# Side_PCB.net
KiCad netlist of a schematic drawn in Altium Designer
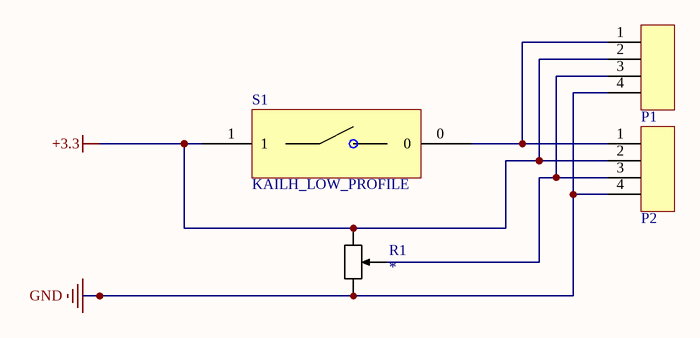
[diagram p0: Side_PCB.SchDoc]

(export (version "E")
  (design (tool "Eeschema 10.0.6"))
  (components
    (comp (ref "P1")
      (value "JST_SE_4PIN")
      (footprint "JST_SE_4PIN")
      (libsource (lib "FF_component_lib") (part "JST_SE_4PIN"))
    )
    (comp (ref "P2")
      (value "JST_SE_4PIN")
      (footprint "JST_SE_4PIN")
      (libsource (lib "FF_component_lib") (part "JST_SE_4PIN"))
    )
    (comp (ref "R1")
      (value "R_POTMETER")
      (fields (field (name "ALTIUM_VALUE") "*"))
      (libsource (lib "FF_component_lib") (part "R_POTMETER"))
    )
    (comp (ref "S1")
      (value "KAILH_LOW_PROFILE")
      (footprint "KAILH_LOW_PROFILE")
      (libsource (lib "FF_component_lib") (part "KAILH_LOW_PROFILE"))
    )
  )
  (nets
    (net (code "1") (name "+3.3") (class "Default")
      (node (ref "P1") (pin "2") (pinfunction "2_2") (pintype "passive"))
      (node (ref "P2") (pin "2") (pinfunction "2_2") (pintype "passive"))
      (node (ref "R1") (pin "1") (pinfunction "1_1") (pintype "passive"))
      (node (ref "S1") (pin "1") (pinfunction "1_1") (pintype "passive"))
    )
    (net (code "2") (name "GND") (class "Default")
      (node (ref "P1") (pin "4") (pinfunction "4_4") (pintype "passive"))
      (node (ref "P2") (pin "4") (pinfunction "4_4") (pintype "passive"))
      (node (ref "R1") (pin "2") (pinfunction "2_2") (pintype "passive"))
    )
    (net (code "3") (name "Net-(P1-Pad1)") (class "Default")
      (node (ref "P1") (pin "1") (pinfunction "1_1") (pintype "passive"))
      (node (ref "P2") (pin "1") (pinfunction "1_1") (pintype "passive"))
      (node (ref "S1") (pin "0") (pinfunction "0_0") (pintype "passive"))
    )
    (net (code "4") (name "Net-(P1-Pad3)") (class "Default")
      (node (ref "P1") (pin "3") (pinfunction "3_3") (pintype "passive"))
      (node (ref "P2") (pin "3") (pinfunction "3_3") (pintype "passive"))
    )
  )
)
